# CoinSensor__TLV333_v1_0.net
KiCad netlist of a schematic drawn in Altium Designer
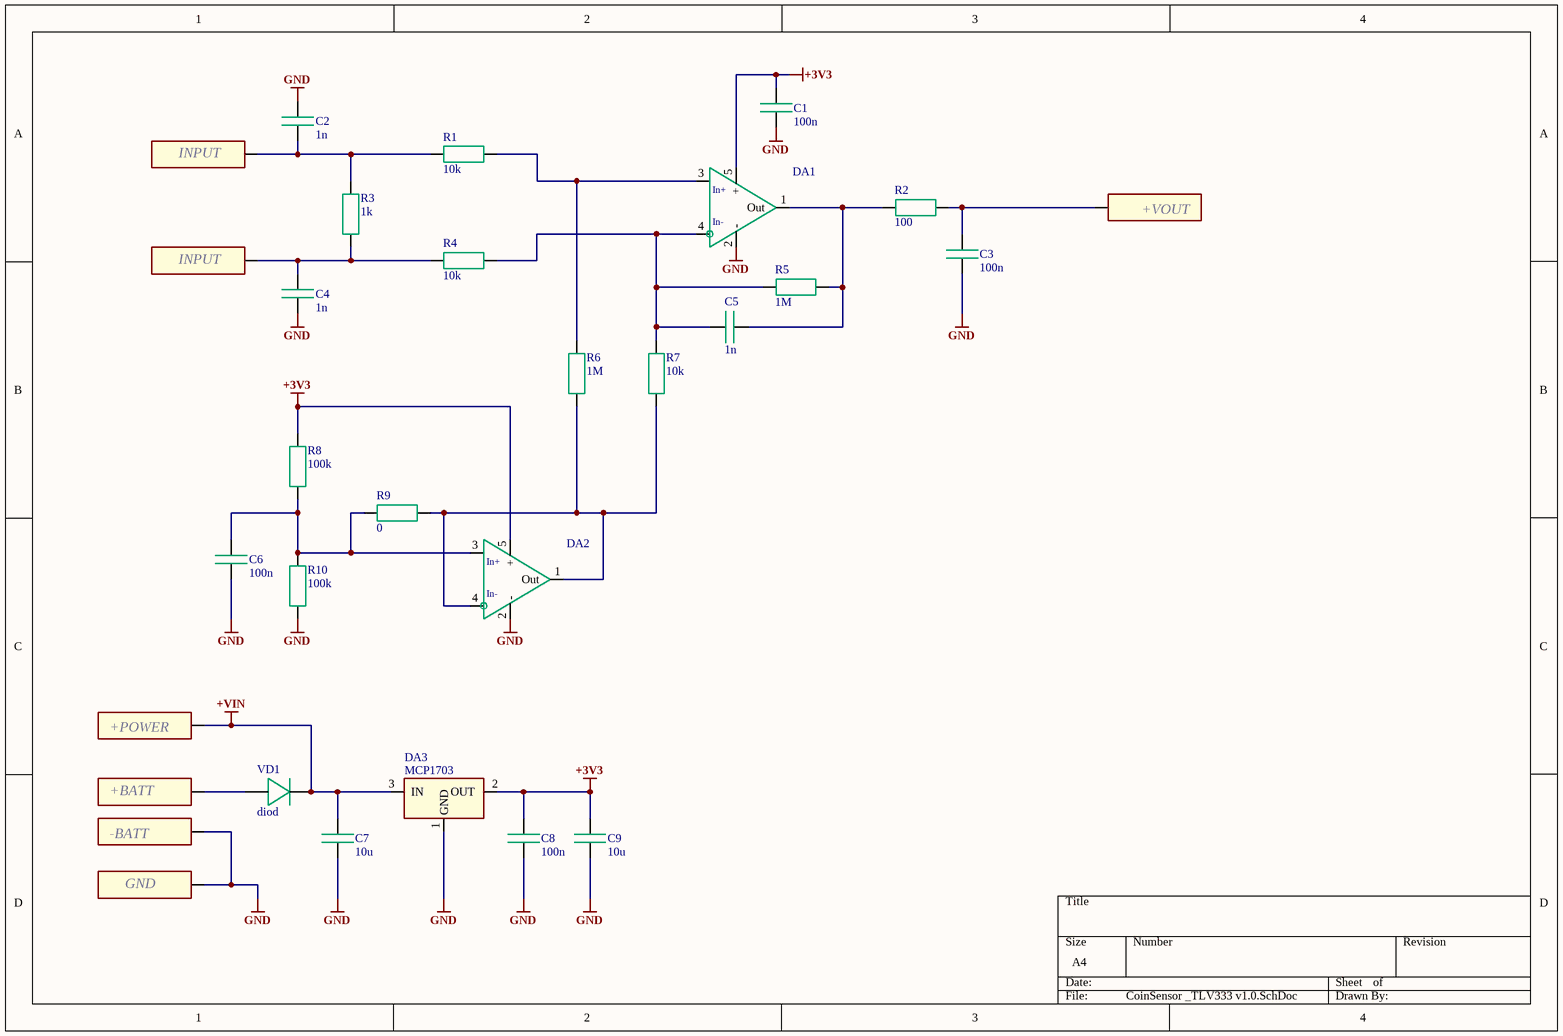
[diagram p0: CoinSensor _TLV333 v1.0.SchDoc]

(export (version "E")
  (design (tool "Eeschema 10.0.6"))
  (components
    (comp (ref "C1")
      (value "100n")
      (footprint "CAP 0603")
      (description "Ceramic capacitor, SMD")
      (fields (field (name "MANUFACTURER") "Samsung") (field (name "TOLERANCE") "±10%"))
      (libsource (lib "altium library") (part "Capacitor"))
    )
    (comp (ref "C2")
      (value "1n")
      (footprint "CAP 0603")
      (description "Ceramic capacitor, SMD")
      (fields (field (name "MANUFACTURER") "Samsung") (field (name "TOLERANCE") "±10%"))
      (libsource (lib "altium library") (part "Capacitor"))
    )
    (comp (ref "C3")
      (value "100n")
      (footprint "CAP 0603")
      (description "Ceramic capacitor, SMD")
      (fields (field (name "MANUFACTURER") "Samsung") (field (name "TOLERANCE") "±10%"))
      (libsource (lib "altium library") (part "Capacitor"))
    )
    (comp (ref "C4")
      (value "1n")
      (footprint "CAP 0603")
      (description "Ceramic capacitor, SMD")
      (fields (field (name "MANUFACTURER") "Samsung") (field (name "TOLERANCE") "±10%"))
      (libsource (lib "altium library") (part "Capacitor"))
    )
    (comp (ref "C5")
      (value "1n")
      (footprint "CAP 0603")
      (description "Ceramic capacitor, SMD")
      (fields (field (name "MANUFACTURER") "Samsung") (field (name "TOLERANCE") "±10%"))
      (libsource (lib "altium library") (part "Capacitor"))
    )
    (comp (ref "C6")
      (value "100n")
      (footprint "CAP 0603")
      (description "Ceramic capacitor, SMD")
      (fields (field (name "MANUFACTURER") "Samsung") (field (name "TOLERANCE") "±10%"))
      (libsource (lib "altium library") (part "Capacitor"))
    )
    (comp (ref "C7")
      (value "10u")
      (footprint "CAP 0603")
      (description "Ceramic capacitor, SMD")
      (fields (field (name "MANUFACTURER") "Samsung") (field (name "TOLERANCE") "±10%"))
      (libsource (lib "altium library") (part "Capacitor"))
    )
    (comp (ref "C8")
      (value "100n")
      (footprint "CAP 0603")
      (description "Ceramic capacitor, SMD")
      (fields (field (name "MANUFACTURER") "Samsung") (field (name "TOLERANCE") "±10%"))
      (libsource (lib "altium library") (part "Capacitor"))
    )
    (comp (ref "C9")
      (value "10u")
      (footprint "CAP 0603")
      (description "Ceramic capacitor, SMD")
      (fields (field (name "MANUFACTURER") "Samsung") (field (name "TOLERANCE") "±10%"))
      (libsource (lib "altium library") (part "Capacitor"))
    )
    (comp (ref "DA1")
      (value "TLV333IDBVR")
      (footprint "SOT-23-5")
      (description "Operation Amplifier, rail-to-rail")
      (fields (field (name "MANUFACTURER") "Texas Instruments"))
      (libsource (lib "altium library") (part "TLV333IDBVR"))
    )
    (comp (ref "DA2")
      (value "TLV333IDBVR")
      (footprint "SOT-23-5")
      (description "Operation Amplifier, rail-to-rail")
      (fields (field (name "MANUFACTURER") "Texas Instruments"))
      (libsource (lib "altium library") (part "TLV333IDBVR"))
    )
    (comp (ref "DA3")
      (value "MCP1703")
      (footprint "SOT-23A")
      (description "Voltage regulator, linear")
      (fields (field (name "MANUFACTURER") "Microchip"))
      (libsource (lib "altium library") (part "MCP1703"))
    )
    (comp (ref "R1")
      (value "10k")
      (footprint "RES 0603")
      (description "Chip resistor, SMD")
      (fields (field (name "MANUFACTURER") "Samsung") (field (name "TOLERANCE") "5%"))
      (libsource (lib "altium library") (part "Resistor"))
    )
    (comp (ref "R2")
      (value "100")
      (footprint "RES 0603")
      (description "Chip resistor, SMD")
      (fields (field (name "MANUFACTURER") "Samsung") (field (name "TOLERANCE") "5%"))
      (libsource (lib "altium library") (part "Resistor"))
    )
    (comp (ref "R3")
      (value "1k")
      (footprint "RES 0603")
      (description "Chip resistor, SMD")
      (fields (field (name "MANUFACTURER") "Samsung") (field (name "TOLERANCE") "5%"))
      (libsource (lib "altium library") (part "Resistor"))
    )
    (comp (ref "R4")
      (value "10k")
      (footprint "RES 0603")
      (description "Chip resistor, SMD")
      (fields (field (name "MANUFACTURER") "Samsung") (field (name "TOLERANCE") "5%"))
      (libsource (lib "altium library") (part "Resistor"))
    )
    (comp (ref "R5")
      (value "1M")
      (footprint "RES 0603")
      (description "Chip resistor, SMD")
      (fields (field (name "MANUFACTURER") "Samsung") (field (name "TOLERANCE") "5%"))
      (libsource (lib "altium library") (part "Resistor"))
    )
    (comp (ref "R6")
      (value "1M")
      (footprint "RES 0603")
      (description "Chip resistor, SMD")
      (fields (field (name "MANUFACTURER") "Samsung") (field (name "TOLERANCE") "5%"))
      (libsource (lib "altium library") (part "Resistor"))
    )
    (comp (ref "R7")
      (value "10k")
      (footprint "RES 0603")
      (description "Chip resistor, SMD")
      (fields (field (name "MANUFACTURER") "Samsung") (field (name "TOLERANCE") "5%"))
      (libsource (lib "altium library") (part "Resistor"))
    )
    (comp (ref "R8")
      (value "100k")
      (footprint "RES 0603")
      (description "Chip resistor, SMD")
      (fields (field (name "MANUFACTURER") "Samsung") (field (name "TOLERANCE") "5%"))
      (libsource (lib "altium library") (part "Resistor"))
    )
    (comp (ref "R9")
      (value "0")
      (footprint "RES 0603")
      (description "Chip resistor, SMD")
      (fields (field (name "MANUFACTURER") "Samsung") (field (name "TOLERANCE") "5%"))
      (libsource (lib "altium library") (part "Resistor"))
    )
    (comp (ref "R10")
      (value "100k")
      (footprint "RES 0603")
      (description "Chip resistor, SMD")
      (fields (field (name "MANUFACTURER") "Samsung") (field (name "TOLERANCE") "5%"))
      (libsource (lib "altium library") (part "Resistor"))
    )
    (comp (ref "VD1")
      (value "diod")
      (footprint "SOD-323")
      (description "Diode schottky")
      (fields (field (name "MANUFACTURER") "ON Semiconductor") (field (name "VOLTAGE") "30V"))
      (libsource (lib "altium library") (part "diod"))
    )
    (comp (ref "X1")
      (value "INPUT")
      (footprint "PLS-1")
      (fields (field (name "NAME") "INPUT") (field (name "MANUFACTURER") "KHADB"))
      (libsource (lib "") (part "PIN_2"))
    )
    (comp (ref "X2")
      (value "+VOUT")
      (footprint "PLS-1")
      (fields (field (name "NAME") "+VOUT") (field (name "MANUFACTURER") "KHADB"))
      (libsource (lib "altium library") (part "PIN"))
    )
    (comp (ref "X3")
      (value "INPUT")
      (footprint "PLS-1")
      (fields (field (name "NAME") "INPUT") (field (name "MANUFACTURER") "KHADB"))
      (libsource (lib "") (part "PIN_2"))
    )
    (comp (ref "X4")
      (value "+VIN")
      (footprint "PLS-1")
      (fields (field (name "NAME") "+POWER") (field (name "MANUFACTURER") "KHADB"))
      (libsource (lib "") (part "PIN_1"))
    )
    (comp (ref "X5")
      (value "+BATT")
      (footprint "PLS-1")
      (fields (field (name "NAME") "+BATT") (field (name "MANUFACTURER") "KHADB"))
      (libsource (lib "") (part "PIN_2"))
    )
    (comp (ref "X6")
      (value "-BATT")
      (footprint "PLS-1")
      (fields (field (name "NAME") "-BATT") (field (name "MANUFACTURER") "KHADB"))
      (libsource (lib "") (part "PIN_1"))
    )
    (comp (ref "X7")
      (value "GND")
      (footprint "PLS-1")
      (fields (field (name "NAME") "GND") (field (name "MANUFACTURER") "KHADB"))
      (libsource (lib "") (part "PIN_2"))
    )
  )
  (nets
    (net (code "1") (name "+3V3") (class "Default")
      (node (ref "C1") (pin "2") (pinfunction "2_2") (pintype "passive"))
      (node (ref "C8") (pin "2") (pinfunction "2_2") (pintype "passive"))
      (node (ref "C9") (pin "2") (pinfunction "2_2") (pintype "passive"))
      (node (ref "DA1") (pin "5") (pinfunction "+_5") (pintype "passive"))
      (node (ref "DA2") (pin "5") (pinfunction "+_5") (pintype "passive"))
      (node (ref "DA3") (pin "2") (pinfunction "OUT_2") (pintype "passive"))
      (node (ref "R8") (pin "1") (pinfunction "1_1") (pintype "passive"))
    )
    (net (code "2") (name "+VIN") (class "Default")
      (node (ref "C7") (pin "2") (pinfunction "2_2") (pintype "passive"))
      (node (ref "DA3") (pin "3") (pinfunction "IN_3") (pintype "passive"))
      (node (ref "VD1") (pin "1") (pinfunction "1_1") (pintype "passive"))
      (node (ref "X4") (pin "1") (pinfunction "1_1") (pintype "passive"))
    )
    (net (code "3") (name "GND") (class "Default")
      (node (ref "C1") (pin "1") (pinfunction "1_1") (pintype "passive"))
      (node (ref "C2") (pin "2") (pinfunction "2_2") (pintype "passive"))
      (node (ref "C3") (pin "2") (pinfunction "2_2") (pintype "passive"))
      (node (ref "C4") (pin "1") (pinfunction "1_1") (pintype "passive"))
      (node (ref "C6") (pin "1") (pinfunction "1_1") (pintype "passive"))
      (node (ref "C7") (pin "1") (pinfunction "1_1") (pintype "passive"))
      (node (ref "C8") (pin "1") (pinfunction "1_1") (pintype "passive"))
      (node (ref "C9") (pin "1") (pinfunction "1_1") (pintype "passive"))
      (node (ref "DA1") (pin "2") (pinfunction "-_2") (pintype "passive"))
      (node (ref "DA2") (pin "2") (pinfunction "-_2") (pintype "passive"))
      (node (ref "DA3") (pin "1") (pinfunction "GND_1") (pintype "passive"))
      (node (ref "R10") (pin "2") (pinfunction "2_2") (pintype "passive"))
      (node (ref "X6") (pin "1") (pinfunction "1_1") (pintype "passive"))
      (node (ref "X7") (pin "1") (pinfunction "1_1") (pintype "passive"))
    )
    (net (code "4") (name "Net-(C2-Pad1)") (class "Default")
      (node (ref "C2") (pin "1") (pinfunction "1_1") (pintype "passive"))
      (node (ref "R1") (pin "2") (pinfunction "2_2") (pintype "passive"))
      (node (ref "R3") (pin "1") (pinfunction "1_1") (pintype "passive"))
      (node (ref "X1") (pin "1") (pinfunction "1_1") (pintype "passive"))
    )
    (net (code "5") (name "Net-(C3-Pad1)") (class "Default")
      (node (ref "C3") (pin "1") (pinfunction "1_1") (pintype "passive"))
      (node (ref "R2") (pin "1") (pinfunction "1_1") (pintype "passive"))
      (node (ref "X2") (pin "1") (pinfunction "1_1") (pintype "passive"))
    )
    (net (code "6") (name "Net-(C4-Pad2)") (class "Default")
      (node (ref "C4") (pin "2") (pinfunction "2_2") (pintype "passive"))
      (node (ref "R3") (pin "2") (pinfunction "2_2") (pintype "passive"))
      (node (ref "R4") (pin "2") (pinfunction "2_2") (pintype "passive"))
      (node (ref "X3") (pin "1") (pinfunction "1_1") (pintype "passive"))
    )
    (net (code "7") (name "Net-(C5-Pad1)") (class "Default")
      (node (ref "C5") (pin "1") (pinfunction "1_1") (pintype "passive"))
      (node (ref "DA1") (pin "4") (pintype "passive"))
      (node (ref "R4") (pin "1") (pinfunction "1_1") (pintype "passive"))
      (node (ref "R5") (pin "1") (pinfunction "1_1") (pintype "passive"))
      (node (ref "R7") (pin "2") (pinfunction "2_2") (pintype "passive"))
    )
    (net (code "8") (name "Net-(C6-Pad2)") (class "Default")
      (node (ref "C6") (pin "2") (pinfunction "2_2") (pintype "passive"))
      (node (ref "DA2") (pin "3") (pintype "passive"))
      (node (ref "R10") (pin "1") (pinfunction "1_1") (pintype "passive"))
      (node (ref "R8") (pin "2") (pinfunction "2_2") (pintype "passive"))
      (node (ref "R9") (pin "1") (pinfunction "1_1") (pintype "passive"))
    )
    (net (code "9") (name "Net-(DA1-Out)") (class "Default")
      (node (ref "C5") (pin "2") (pinfunction "2_2") (pintype "passive"))
      (node (ref "DA1") (pin "1") (pinfunction "Out_1") (pintype "passive"))
      (node (ref "R2") (pin "2") (pinfunction "2_2") (pintype "passive"))
      (node (ref "R5") (pin "2") (pinfunction "2_2") (pintype "passive"))
    )
    (net (code "10") (name "Net-(DA1-Pad3)") (class "Default")
      (node (ref "DA1") (pin "3") (pintype "passive"))
      (node (ref "R1") (pin "1") (pinfunction "1_1") (pintype "passive"))
      (node (ref "R6") (pin "2") (pinfunction "2_2") (pintype "passive"))
    )
    (net (code "11") (name "Net-(DA2-Out)") (class "Default")
      (node (ref "DA2") (pin "1") (pinfunction "Out_1") (pintype "passive"))
      (node (ref "DA2") (pin "4") (pintype "passive"))
      (node (ref "R6") (pin "1") (pinfunction "1_1") (pintype "passive"))
      (node (ref "R7") (pin "1") (pinfunction "1_1") (pintype "passive"))
      (node (ref "R9") (pin "2") (pinfunction "2_2") (pintype "passive"))
    )
    (net (code "12") (name "Net-(VD1-Pad2)") (class "Default")
      (node (ref "VD1") (pin "2") (pinfunction "2_2") (pintype "passive"))
      (node (ref "X5") (pin "1") (pinfunction "1_1") (pintype "passive"))
    )
  )
)
